# ahe_v1_0.net
KiCad netlist of a schematic drawn in EAGLE
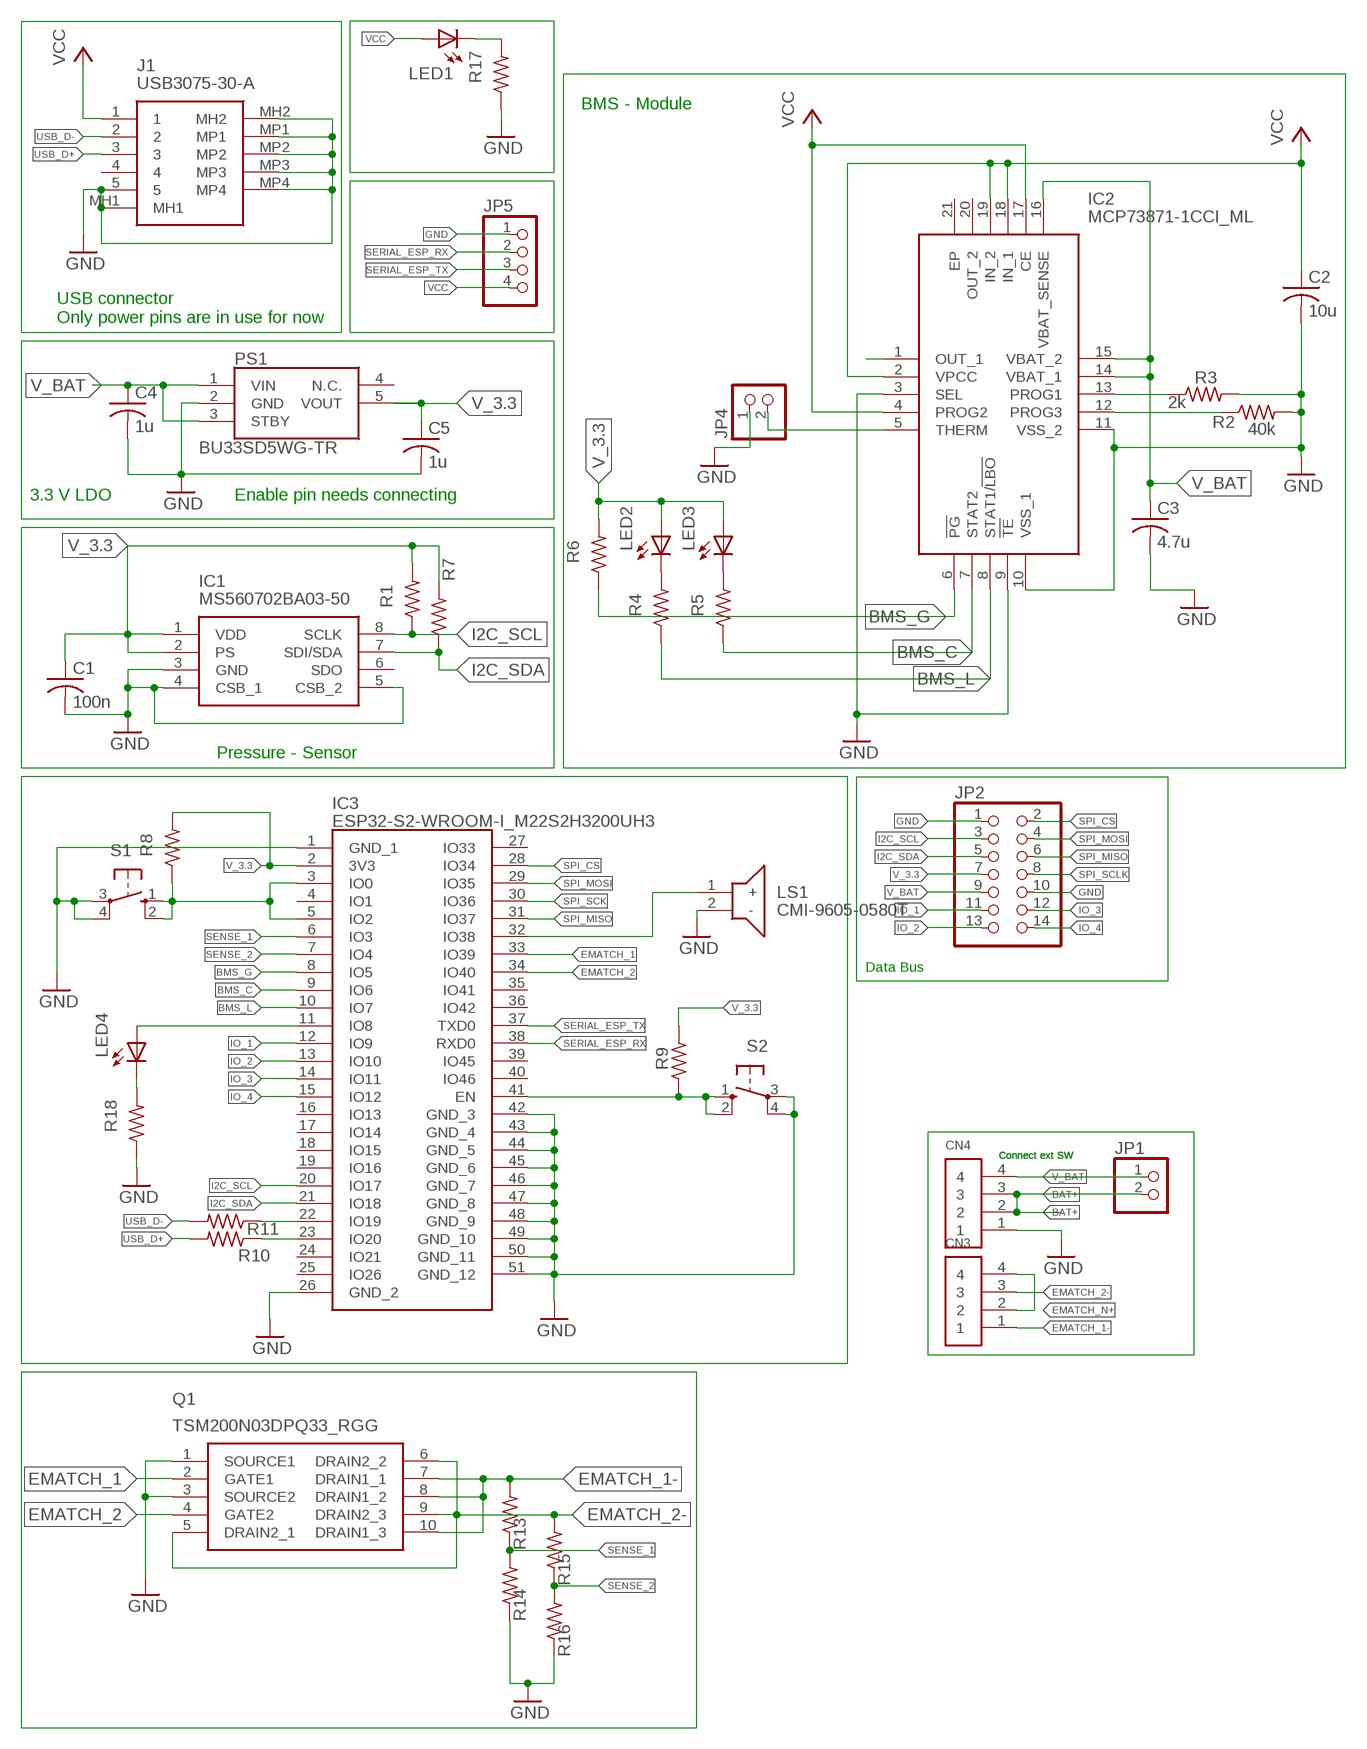
[diagram p0: schematic, sheet 1]

(export (version "E")
  (design (tool "Eeschema 10.0.6"))
  (components
    (comp (ref "C1")
      (value "100n")
      (footprint "eagle-import:C0805")
      (libsource (lib "eagle-import") (part "C-USC0805"))
    )
    (comp (ref "C2")
      (value "10u")
      (footprint "eagle-import:C0805")
      (libsource (lib "eagle-import") (part "C-USC0805"))
    )
    (comp (ref "C3")
      (value "4.7u")
      (footprint "eagle-import:C0805")
      (libsource (lib "eagle-import") (part "C-USC0805"))
    )
    (comp (ref "C4")
      (value "1u")
      (footprint "eagle-import:C0805")
      (libsource (lib "eagle-import") (part "C-USC0805"))
    )
    (comp (ref "C5")
      (value "1u")
      (footprint "eagle-import:C0805")
      (libsource (lib "eagle-import") (part "C-USC0805"))
    )
    (comp (ref "CN3")
      (value "1X4-3.5MM")
      (footprint "eagle-import:1X04-3.5MM")
      (libsource (lib "eagle-import") (part "1X4-3.5MM"))
    )
    (comp (ref "CN4")
      (value "1X4-3.5MM")
      (footprint "eagle-import:1X04-3.5MM")
      (libsource (lib "eagle-import") (part "1X4-3.5MM"))
    )
    (comp (ref "IC1")
      (value "MS560702BA03-50")
      (footprint "eagle-import:MS5607-02BA03")
      (fields (field (name "MOUSER_PART_NUMBER") "824-MS560702BA03-50"))
      (libsource (lib "eagle-import") (part "MS560702BA03-50"))
    )
    (comp (ref "IC2")
      (value "MCP73871-1CCI_ML")
      (footprint "eagle-import:QFN50P400X400X100-21N")
      (fields
        (field (name "MANUFACTURER_PART_NUMBER") "MCP73871-1CCI/ML")
        (field (name "MOUSER_PART_NUMBER") "579-MCP73871-1CCI/ML")
      )
      (libsource (lib "eagle-import") (part "MCP73871-1CCI_ML"))
    )
    (comp (ref "IC3")
      (value "ESP32-S2-WROOM-I_M22S2H3200UH3")
      (footprint "eagle-import:ESP32S2WROOMIM22S2H3200UH3Q0")
      (fields
        (field (name "MANUFACTURER_PART_NUMBER") "ESP32-S2-WROOM-I(M22S2H3200UH3Q0)")
        (field (name "MOUSER_PART_NUMBER") "356-ESP32S2WRMI320UH")
      )
      (libsource (lib "eagle-import") (part "ESP32-S2-WROOM-I_M22S2H3200UH3"))
    )
    (comp (ref "J1")
      (value "USB3075-30-A")
      (footprint "eagle-import:USB307530A")
      (fields (field (name "MOUSER_PART_NUMBER") "640-USB3075-30-A"))
      (libsource (lib "eagle-import") (part "USB3075-30-A"))
    )
    (comp (ref "JP1")
      (value "PINHD-1X2")
      (footprint "eagle-import:1X02")
      (libsource (lib "eagle-import") (part "PINHD-1X2"))
    )
    (comp (ref "JP2")
      (value "PINHD-2X7")
      (footprint "eagle-import:2X07")
      (libsource (lib "eagle-import") (part "PINHD-2X7"))
    )
    (comp (ref "JP4")
      (value "PINHD-1X2")
      (footprint "eagle-import:1X02")
      (libsource (lib "eagle-import") (part "PINHD-1X2"))
    )
    (comp (ref "JP5")
      (value "PINHD-1X4")
      (footprint "eagle-import:1X04")
      (libsource (lib "eagle-import") (part "PINHD-1X4"))
    )
    (comp (ref "LED1")
      (value "LEDCHIPLED_0805")
      (footprint "eagle-import:CHIPLED_0805")
      (libsource (lib "eagle-import") (part "LEDCHIPLED_0805"))
    )
    (comp (ref "LED2")
      (value "LEDCHIPLED_0805")
      (footprint "eagle-import:CHIPLED_0805")
      (libsource (lib "eagle-import") (part "LEDCHIPLED_0805"))
    )
    (comp (ref "LED3")
      (value "LEDCHIPLED_0805")
      (footprint "eagle-import:CHIPLED_0805")
      (libsource (lib "eagle-import") (part "LEDCHIPLED_0805"))
    )
    (comp (ref "LED4")
      (value "LEDCHIPLED_0805")
      (footprint "eagle-import:CHIPLED_0805")
      (libsource (lib "eagle-import") (part "LEDCHIPLED_0805"))
    )
    (comp (ref "LS1")
      (value "CMI-9605-0580T")
      (footprint "eagle-import:CMI96050580T")
      (fields (field (name "MOUSER_PART_NUMBER") "490-CMI-9605-0580T"))
      (libsource (lib "eagle-import") (part "CMI-9605-0580T"))
    )
    (comp (ref "PS1")
      (value "BU33SD5WG-TR")
      (footprint "eagle-import:SOT95P280X125-5N")
      (fields (field (name "MOUSER_PART_NUMBER") "755-BU33SD5WG-TR"))
      (libsource (lib "eagle-import") (part "BU33SD5WG-TR"))
    )
    (comp (ref "Q1")
      (value "TSM200N03DPQ33_RGG")
      (footprint "eagle-import:TSM200N03DPQ33RGG")
      (fields
        (field (name "MANUFACTURER_PART_NUMBER") "TSM200N03DPQ33 RGG")
        (field (name "MOUSER_PART_NUMBER") "821-TSM200N03DPQ33RG")
      )
      (libsource (lib "eagle-import") (part "TSM200N03DPQ33_RGG"))
    )
    (comp (ref "R1")
      (value "10k")
      (footprint "eagle-import:R0805")
      (libsource (lib "eagle-import") (part "R-US_R0805"))
    )
    (comp (ref "R2")
      (value "40k")
      (footprint "eagle-import:R0805")
      (libsource (lib "eagle-import") (part "R-US_R0805"))
    )
    (comp (ref "R3")
      (value "2k")
      (footprint "eagle-import:R0805")
      (libsource (lib "eagle-import") (part "R-US_R0805"))
    )
    (comp (ref "R4")
      (value "330")
      (footprint "eagle-import:R0805")
      (libsource (lib "eagle-import") (part "R-US_R0805"))
    )
    (comp (ref "R5")
      (value "330")
      (footprint "eagle-import:R0805")
      (libsource (lib "eagle-import") (part "R-US_R0805"))
    )
    (comp (ref "R6")
      (value "10k")
      (footprint "eagle-import:R0805")
      (libsource (lib "eagle-import") (part "R-US_R0805"))
    )
    (comp (ref "R7")
      (value "10k")
      (footprint "eagle-import:R0805")
      (libsource (lib "eagle-import") (part "R-US_R0805"))
    )
    (comp (ref "R8")
      (value "10k")
      (footprint "eagle-import:R0805")
      (libsource (lib "eagle-import") (part "R-US_R0805"))
    )
    (comp (ref "R9")
      (value "10k")
      (footprint "eagle-import:R0805")
      (libsource (lib "eagle-import") (part "R-US_R0805"))
    )
    (comp (ref "R10")
      (value "33")
      (footprint "eagle-import:R0805")
      (libsource (lib "eagle-import") (part "R-US_R0805"))
    )
    (comp (ref "R11")
      (value "33")
      (footprint "eagle-import:R0805")
      (libsource (lib "eagle-import") (part "R-US_R0805"))
    )
    (comp (ref "R13")
      (value "100k")
      (footprint "eagle-import:R0805")
      (libsource (lib "eagle-import") (part "R-US_R0805"))
    )
    (comp (ref "R14")
      (value "27k")
      (footprint "eagle-import:R0805")
      (libsource (lib "eagle-import") (part "R-US_R0805"))
    )
    (comp (ref "R15")
      (value "100k")
      (footprint "eagle-import:R0805")
      (libsource (lib "eagle-import") (part "R-US_R0805"))
    )
    (comp (ref "R16")
      (value "27k")
      (footprint "eagle-import:R0805")
      (libsource (lib "eagle-import") (part "R-US_R0805"))
    )
    (comp (ref "R17")
      (value "330")
      (footprint "eagle-import:R0805")
      (libsource (lib "eagle-import") (part "R-US_R0805"))
    )
    (comp (ref "R18")
      (value "330")
      (footprint "eagle-import:R0805")
      (libsource (lib "eagle-import") (part "R-US_R0805"))
    )
    (comp (ref "S1")
      (value "10-XX")
      (footprint "eagle-import:B3F-10XX")
      (fields (field (name "MPN") "B3F-1000"))
      (libsource (lib "eagle-import") (part "10-XX"))
    )
    (comp (ref "S2")
      (value "10-XX")
      (footprint "eagle-import:B3F-10XX")
      (fields (field (name "MPN") "B3F-1000"))
      (libsource (lib "eagle-import") (part "10-XX"))
    )
  )
  (nets
    (net (code "1") (name "BAT+") (class "Default")
      (node (ref "CN4") (pin "2") (pinfunction "2_2") (pintype "bidirectional"))
      (node (ref "CN4") (pin "3") (pinfunction "3_3") (pintype "bidirectional"))
      (node (ref "JP1") (pin "2") (pinfunction "2_2") (pintype "passive"))
    )
    (net (code "2") (name "BMS_C") (class "Default")
      (node (ref "IC2") (pin "7") (pinfunction "STAT2_7") (pintype "bidirectional"))
      (node (ref "IC3") (pin "9") (pinfunction "IO6_9") (pintype "bidirectional"))
      (node (ref "R5") (pin "1") (pinfunction "1_1") (pintype "passive"))
    )
    (net (code "3") (name "BMS_G") (class "Default")
      (node (ref "IC2") (pin "6") (pinfunction "~{PG}_6") (pintype "bidirectional"))
      (node (ref "IC3") (pin "8") (pinfunction "IO5_8") (pintype "bidirectional"))
      (node (ref "R6") (pin "1") (pinfunction "1_1") (pintype "passive"))
    )
    (net (code "4") (name "BMS_L") (class "Default")
      (node (ref "IC2") (pin "8") (pinfunction "STAT1/~{LBO}_8") (pintype "bidirectional"))
      (node (ref "IC3") (pin "10") (pinfunction "IO7_10") (pintype "bidirectional"))
      (node (ref "R4") (pin "1") (pinfunction "1_1") (pintype "passive"))
    )
    (net (code "5") (name "EMATCH_1") (class "Default")
      (node (ref "IC3") (pin "33") (pinfunction "IO39_33") (pintype "bidirectional"))
      (node (ref "Q1") (pin "2") (pinfunction "GATE1_2") (pintype "bidirectional"))
    )
    (net (code "6") (name "EMATCH_1-") (class "Default")
      (node (ref "CN3") (pin "1") (pinfunction "1_1") (pintype "bidirectional"))
      (node (ref "Q1") (pin "10") (pinfunction "DRAIN1_3_10") (pintype "bidirectional"))
      (node (ref "Q1") (pin "7") (pinfunction "DRAIN1_1_7") (pintype "bidirectional"))
      (node (ref "Q1") (pin "8") (pinfunction "DRAIN1_2_8") (pintype "bidirectional"))
      (node (ref "R13") (pin "2") (pinfunction "2_2") (pintype "passive"))
    )
    (net (code "7") (name "EMATCH_2") (class "Default")
      (node (ref "IC3") (pin "34") (pinfunction "IO40_34") (pintype "bidirectional"))
      (node (ref "Q1") (pin "4") (pinfunction "GATE2_4") (pintype "bidirectional"))
    )
    (net (code "8") (name "EMATCH_2-") (class "Default")
      (node (ref "CN3") (pin "3") (pinfunction "3_3") (pintype "bidirectional"))
      (node (ref "Q1") (pin "5") (pinfunction "DRAIN2_1_5") (pintype "bidirectional"))
      (node (ref "Q1") (pin "6") (pinfunction "DRAIN2_2_6") (pintype "bidirectional"))
      (node (ref "Q1") (pin "9") (pinfunction "DRAIN2_3_9") (pintype "bidirectional"))
      (node (ref "R15") (pin "2") (pinfunction "2_2") (pintype "passive"))
    )
    (net (code "9") (name "EMATCH_N+") (class "Default")
      (node (ref "CN3") (pin "2") (pinfunction "2_2") (pintype "bidirectional"))
      (node (ref "CN3") (pin "4") (pinfunction "4_4") (pintype "bidirectional"))
    )
    (net (code "10") (name "GND") (class "Default")
      (node (ref "C1") (pin "2") (pinfunction "2_2") (pintype "passive"))
      (node (ref "C2") (pin "2") (pinfunction "2_2") (pintype "passive"))
      (node (ref "C3") (pin "2") (pinfunction "2_2") (pintype "passive"))
      (node (ref "C4") (pin "2") (pinfunction "2_2") (pintype "passive"))
      (node (ref "C5") (pin "2") (pinfunction "2_2") (pintype "passive"))
      (node (ref "CN4") (pin "1") (pinfunction "1_1") (pintype "bidirectional"))
      (node (ref "IC1") (pin "3") (pinfunction "GND_3") (pintype "power_in"))
      (node (ref "IC1") (pin "4") (pinfunction "CSB_1_4") (pintype "input"))
      (node (ref "IC1") (pin "5") (pinfunction "CSB_2_5") (pintype "input"))
      (node (ref "IC2") (pin "10") (pinfunction "VSS_1_10") (pintype "bidirectional"))
      (node (ref "IC2") (pin "11") (pinfunction "VSS_2_11") (pintype "bidirectional"))
      (node (ref "IC2") (pin "3") (pinfunction "SEL_3") (pintype "bidirectional"))
      (node (ref "IC2") (pin "9") (pinfunction "~{TE}_9") (pintype "bidirectional"))
      (node (ref "IC3") (pin "1") (pinfunction "GND_1_1") (pintype "bidirectional"))
      (node (ref "IC3") (pin "26") (pinfunction "GND_2_26") (pintype "bidirectional"))
      (node (ref "IC3") (pin "42") (pinfunction "GND_3_42") (pintype "bidirectional"))
      (node (ref "IC3") (pin "43") (pinfunction "GND_4_43") (pintype "bidirectional"))
      (node (ref "IC3") (pin "44") (pinfunction "GND_5_44") (pintype "bidirectional"))
      (node (ref "IC3") (pin "45") (pinfunction "GND_6_45") (pintype "bidirectional"))
      (node (ref "IC3") (pin "46") (pinfunction "GND_7_46") (pintype "bidirectional"))
      (node (ref "IC3") (pin "47") (pinfunction "GND_8_47") (pintype "bidirectional"))
      (node (ref "IC3") (pin "48") (pinfunction "GND_9_48") (pintype "bidirectional"))
      (node (ref "IC3") (pin "49") (pinfunction "GND_10_49") (pintype "bidirectional"))
      (node (ref "IC3") (pin "50") (pinfunction "GND_11_50") (pintype "bidirectional"))
      (node (ref "IC3") (pin "51") (pinfunction "GND_12_51") (pintype "bidirectional"))
      (node (ref "J1") (pin "5") (pinfunction "5_5") (pintype "bidirectional"))
      (node (ref "J1") (pin "MH1") (pinfunction "MH1_MH1") (pintype "bidirectional"))
      (node (ref "J1") (pin "MH2") (pinfunction "MH2_MH2") (pintype "bidirectional"))
      (node (ref "J1") (pin "MP1") (pinfunction "MP1_MP1") (pintype "bidirectional"))
      (node (ref "J1") (pin "MP2") (pinfunction "MP2_MP2") (pintype "bidirectional"))
      (node (ref "J1") (pin "MP3") (pinfunction "MP3_MP3") (pintype "bidirectional"))
      (node (ref "J1") (pin "MP4") (pinfunction "MP4_MP4") (pintype "bidirectional"))
      (node (ref "JP2") (pin "1") (pinfunction "1_1") (pintype "passive"))
      (node (ref "JP2") (pin "10") (pinfunction "10_10") (pintype "passive"))
      (node (ref "JP4") (pin "1") (pinfunction "1_1") (pintype "passive"))
      (node (ref "JP5") (pin "1") (pinfunction "1_1") (pintype "passive"))
      (node (ref "LS1") (pin "2") (pinfunction "-_2") (pintype "bidirectional"))
      (node (ref "PS1") (pin "2") (pinfunction "GND_2") (pintype "bidirectional"))
      (node (ref "Q1") (pin "1") (pinfunction "SOURCE1_1") (pintype "bidirectional"))
      (node (ref "Q1") (pin "3") (pinfunction "SOURCE2_3") (pintype "bidirectional"))
      (node (ref "R14") (pin "1") (pinfunction "1_1") (pintype "passive"))
      (node (ref "R16") (pin "1") (pinfunction "1_1") (pintype "passive"))
      (node (ref "R17") (pin "1") (pinfunction "1_1") (pintype "passive"))
      (node (ref "R18") (pin "1") (pinfunction "1_1") (pintype "passive"))
      (node (ref "R2") (pin "2") (pinfunction "2_2") (pintype "passive"))
      (node (ref "R3") (pin "2") (pinfunction "2_2") (pintype "passive"))
      (node (ref "S1") (pin "3") (pinfunction "P_3") (pintype "passive"))
      (node (ref "S1") (pin "4") (pinfunction "P1_4") (pintype "passive"))
      (node (ref "S2") (pin "3") (pinfunction "P_3") (pintype "passive"))
      (node (ref "S2") (pin "4") (pinfunction "P1_4") (pintype "passive"))
    )
    (net (code "11") (name "I2C_SCL") (class "Default")
      (node (ref "IC1") (pin "8") (pinfunction "SCLK_8") (pintype "input"))
      (node (ref "IC3") (pin "20") (pinfunction "IO17_20") (pintype "bidirectional"))
      (node (ref "JP2") (pin "3") (pinfunction "3_3") (pintype "passive"))
      (node (ref "R1") (pin "1") (pinfunction "1_1") (pintype "passive"))
    )
    (net (code "12") (name "I2C_SDA") (class "Default")
      (node (ref "IC1") (pin "7") (pinfunction "SDI/SDA_7") (pintype "bidirectional"))
      (node (ref "IC3") (pin "21") (pinfunction "IO18_21") (pintype "bidirectional"))
      (node (ref "JP2") (pin "5") (pinfunction "5_5") (pintype "passive"))
      (node (ref "R7") (pin "1") (pinfunction "1_1") (pintype "passive"))
    )
    (net (code "13") (name "IO_1") (class "Default")
      (node (ref "IC3") (pin "12") (pinfunction "IO9_12") (pintype "bidirectional"))
      (node (ref "JP2") (pin "11") (pinfunction "11_11") (pintype "passive"))
    )
    (net (code "14") (name "IO_2") (class "Default")
      (node (ref "IC3") (pin "13") (pinfunction "IO10_13") (pintype "bidirectional"))
      (node (ref "JP2") (pin "13") (pinfunction "13_13") (pintype "passive"))
    )
    (net (code "15") (name "IO_3") (class "Default")
      (node (ref "IC3") (pin "14") (pinfunction "IO11_14") (pintype "bidirectional"))
      (node (ref "JP2") (pin "12") (pinfunction "12_12") (pintype "passive"))
    )
    (net (code "16") (name "IO_4") (class "Default")
      (node (ref "IC3") (pin "15") (pinfunction "IO12_15") (pintype "bidirectional"))
      (node (ref "JP2") (pin "14") (pinfunction "14_14") (pintype "passive"))
    )
    (net (code "17") (name "Net-(IC2-PROG1)") (class "Default")
      (node (ref "IC2") (pin "13") (pinfunction "PROG1_13") (pintype "bidirectional"))
      (node (ref "R3") (pin "1") (pinfunction "1_1") (pintype "passive"))
    )
    (net (code "18") (name "Net-(IC2-PROG3)") (class "Default")
      (node (ref "IC2") (pin "12") (pinfunction "PROG3_12") (pintype "bidirectional"))
      (node (ref "R2") (pin "1") (pinfunction "1_1") (pintype "passive"))
    )
    (net (code "19") (name "Net-(IC2-THERM)") (class "Default")
      (node (ref "IC2") (pin "5") (pinfunction "THERM_5") (pintype "bidirectional"))
      (node (ref "JP4") (pin "2") (pinfunction "2_2") (pintype "passive"))
    )
    (net (code "20") (name "Net-(IC3-EN)") (class "Default")
      (node (ref "IC3") (pin "41") (pinfunction "EN_41") (pintype "bidirectional"))
      (node (ref "R9") (pin "1") (pinfunction "1_1") (pintype "passive"))
      (node (ref "S2") (pin "1") (pinfunction "S_1") (pintype "passive"))
      (node (ref "S2") (pin "2") (pinfunction "S1_2") (pintype "passive"))
    )
    (net (code "21") (name "Net-(IC3-IO0)") (class "Default")
      (node (ref "IC3") (pin "3") (pinfunction "IO0_3") (pintype "bidirectional"))
      (node (ref "IC3") (pin "5") (pinfunction "IO2_5") (pintype "bidirectional"))
      (node (ref "R8") (pin "1") (pinfunction "1_1") (pintype "passive"))
      (node (ref "S1") (pin "1") (pinfunction "S_1") (pintype "passive"))
      (node (ref "S1") (pin "2") (pinfunction "S1_2") (pintype "passive"))
    )
    (net (code "22") (name "Net-(IC3-IO8)") (class "Default")
      (node (ref "IC3") (pin "11") (pinfunction "IO8_11") (pintype "bidirectional"))
      (node (ref "LED4") (pin "A") (pinfunction "A_A") (pintype "passive"))
    )
    (net (code "23") (name "Net-(IC3-IO19)") (class "Default")
      (node (ref "IC3") (pin "22") (pinfunction "IO19_22") (pintype "bidirectional"))
      (node (ref "R11") (pin "1") (pinfunction "1_1") (pintype "passive"))
    )
    (net (code "24") (name "Net-(IC3-IO20)") (class "Default")
      (node (ref "IC3") (pin "23") (pinfunction "IO20_23") (pintype "bidirectional"))
      (node (ref "R10") (pin "1") (pinfunction "1_1") (pintype "passive"))
    )
    (net (code "25") (name "Net-(IC3-IO38)") (class "Default")
      (node (ref "IC3") (pin "32") (pinfunction "IO38_32") (pintype "bidirectional"))
      (node (ref "LS1") (pin "1") (pinfunction "+_1") (pintype "bidirectional"))
    )
    (net (code "26") (name "Net-(LED1-PadC)") (class "Default")
      (node (ref "LED1") (pin "C") (pinfunction "C_C") (pintype "passive"))
      (node (ref "R17") (pin "2") (pinfunction "2_2") (pintype "passive"))
    )
    (net (code "27") (name "Net-(LED2-PadC)") (class "Default")
      (node (ref "LED2") (pin "C") (pinfunction "C_C") (pintype "passive"))
      (node (ref "R4") (pin "2") (pinfunction "2_2") (pintype "passive"))
    )
    (net (code "28") (name "Net-(LED3-PadC)") (class "Default")
      (node (ref "LED3") (pin "C") (pinfunction "C_C") (pintype "passive"))
      (node (ref "R5") (pin "2") (pinfunction "2_2") (pintype "passive"))
    )
    (net (code "29") (name "Net-(LED4-PadC)") (class "Default")
      (node (ref "LED4") (pin "C") (pinfunction "C_C") (pintype "passive"))
      (node (ref "R18") (pin "2") (pinfunction "2_2") (pintype "passive"))
    )
    (net (code "30") (name "SENSE_1") (class "Default")
      (node (ref "IC3") (pin "6") (pinfunction "IO3_6") (pintype "bidirectional"))
      (node (ref "R13") (pin "1") (pinfunction "1_1") (pintype "passive"))
      (node (ref "R14") (pin "2") (pinfunction "2_2") (pintype "passive"))
    )
    (net (code "31") (name "SENSE_2") (class "Default")
      (node (ref "IC3") (pin "7") (pinfunction "IO4_7") (pintype "bidirectional"))
      (node (ref "R15") (pin "1") (pinfunction "1_1") (pintype "passive"))
      (node (ref "R16") (pin "2") (pinfunction "2_2") (pintype "passive"))
    )
    (net (code "32") (name "SERIAL_ESP_RX") (class "Default")
      (node (ref "IC3") (pin "38") (pinfunction "RXD0_38") (pintype "bidirectional"))
      (node (ref "JP5") (pin "2") (pinfunction "2_2") (pintype "passive"))
    )
    (net (code "33") (name "SERIAL_ESP_TX") (class "Default")
      (node (ref "IC3") (pin "37") (pinfunction "TXD0_37") (pintype "bidirectional"))
      (node (ref "JP5") (pin "3") (pinfunction "3_3") (pintype "passive"))
    )
    (net (code "34") (name "SPI_CS") (class "Default")
      (node (ref "IC3") (pin "28") (pinfunction "IO34_28") (pintype "bidirectional"))
      (node (ref "JP2") (pin "2") (pinfunction "2_2") (pintype "passive"))
    )
    (net (code "35") (name "SPI_MISO") (class "Default")
      (node (ref "IC3") (pin "31") (pinfunction "IO37_31") (pintype "bidirectional"))
      (node (ref "JP2") (pin "6") (pinfunction "6_6") (pintype "passive"))
    )
    (net (code "36") (name "SPI_MOSI") (class "Default")
      (node (ref "IC3") (pin "29") (pinfunction "IO35_29") (pintype "bidirectional"))
      (node (ref "JP2") (pin "4") (pinfunction "4_4") (pintype "passive"))
    )
    (net (code "37") (name "SPI_SCK") (class "Default")
      (node (ref "IC3") (pin "30") (pinfunction "IO36_30") (pintype "bidirectional"))
    )
    (net (code "38") (name "SPI_SCLK") (class "Default")
      (node (ref "JP2") (pin "8") (pinfunction "8_8") (pintype "passive"))
    )
    (net (code "39") (name "USB_D+") (class "Default")
      (node (ref "J1") (pin "3") (pinfunction "3_3") (pintype "bidirectional"))
      (node (ref "R10") (pin "2") (pinfunction "2_2") (pintype "passive"))
    )
    (net (code "40") (name "USB_D-") (class "Default")
      (node (ref "J1") (pin "2") (pinfunction "2_2") (pintype "bidirectional"))
      (node (ref "R11") (pin "2") (pinfunction "2_2") (pintype "passive"))
    )
    (net (code "41") (name "VCC") (class "Default")
      (node (ref "C2") (pin "1") (pinfunction "1_1") (pintype "passive"))
      (node (ref "IC2") (pin "17") (pinfunction "CE_17") (pintype "bidirectional"))
      (node (ref "IC2") (pin "18") (pinfunction "IN_1_18") (pintype "bidirectional"))
      (node (ref "IC2") (pin "19") (pinfunction "IN_2_19") (pintype "bidirectional"))
      (node (ref "IC2") (pin "2") (pinfunction "VPCC_2") (pintype "bidirectional"))
      (node (ref "IC2") (pin "4") (pinfunction "PROG2_4") (pintype "bidirectional"))
      (node (ref "J1") (pin "1") (pinfunction "1_1") (pintype "bidirectional"))
      (node (ref "JP5") (pin "4") (pinfunction "4_4") (pintype "passive"))
      (node (ref "LED1") (pin "A") (pinfunction "A_A") (pintype "passive"))
    )
    (net (code "42") (name "V_3.3") (class "Default")
      (node (ref "C1") (pin "1") (pinfunction "1_1") (pintype "passive"))
      (node (ref "C5") (pin "1") (pinfunction "1_1") (pintype "passive"))
      (node (ref "IC1") (pin "1") (pinfunction "VDD_1") (pintype "power_in"))
      (node (ref "IC1") (pin "2") (pinfunction "PS_2") (pintype "input"))
      (node (ref "IC3") (pin "2") (pinfunction "3V3_2") (pintype "bidirectional"))
      (node (ref "JP2") (pin "7") (pinfunction "7_7") (pintype "passive"))
      (node (ref "LED2") (pin "A") (pinfunction "A_A") (pintype "passive"))
      (node (ref "LED3") (pin "A") (pinfunction "A_A") (pintype "passive"))
      (node (ref "PS1") (pin "5") (pinfunction "VOUT_5") (pintype "bidirectional"))
      (node (ref "R1") (pin "2") (pinfunction "2_2") (pintype "passive"))
      (node (ref "R6") (pin "2") (pinfunction "2_2") (pintype "passive"))
      (node (ref "R7") (pin "2") (pinfunction "2_2") (pintype "passive"))
      (node (ref "R8") (pin "2") (pinfunction "2_2") (pintype "passive"))
      (node (ref "R9") (pin "2") (pinfunction "2_2") (pintype "passive"))
    )
    (net (code "43") (name "V_BAT") (class "Default")
      (node (ref "C3") (pin "1") (pinfunction "1_1") (pintype "passive"))
      (node (ref "C4") (pin "1") (pinfunction "1_1") (pintype "passive"))
      (node (ref "CN4") (pin "4") (pinfunction "4_4") (pintype "bidirectional"))
      (node (ref "IC2") (pin "14") (pinfunction "VBAT_1_14") (pintype "bidirectional"))
      (node (ref "IC2") (pin "15") (pinfunction "VBAT_2_15") (pintype "bidirectional"))
      (node (ref "IC2") (pin "16") (pinfunction "VBAT_SENSE_16") (pintype "bidirectional"))
      (node (ref "JP1") (pin "1") (pinfunction "1_1") (pintype "passive"))
      (node (ref "JP2") (pin "9") (pinfunction "9_9") (pintype "passive"))
      (node (ref "PS1") (pin "1") (pinfunction "VIN_1") (pintype "bidirectional"))
      (node (ref "PS1") (pin "3") (pinfunction "STBY_3") (pintype "bidirectional"))
    )
    (net (code "44") (name "unconnected-(IC1-SDO-Pad6)") (class "Default")
      (node (ref "IC1") (pin "6") (pinfunction "SDO_6") (pintype "output"))
    )
    (net (code "45") (name "unconnected-(IC2-EP-Pad21)") (class "Default")
      (node (ref "IC2") (pin "21") (pinfunction "EP_21") (pintype "bidirectional"))
    )
    (net (code "46") (name "unconnected-(IC2-OUT_1-Pad1)") (class "Default")
      (node (ref "IC2") (pin "1") (pinfunction "OUT_1_1") (pintype "bidirectional"))
    )
    (net (code "47") (name "unconnected-(IC2-OUT_2-Pad20)") (class "Default")
      (node (ref "IC2") (pin "20") (pinfunction "OUT_2_20") (pintype "bidirectional"))
    )
    (net (code "48") (name "unconnected-(IC3-IO1-Pad4)") (class "Default")
      (node (ref "IC3") (pin "4") (pinfunction "IO1_4") (pintype "bidirectional"))
    )
    (net (code "49") (name "unconnected-(IC3-IO13-Pad16)") (class "Default")
      (node (ref "IC3") (pin "16") (pinfunction "IO13_16") (pintype "bidirectional"))
    )
    (net (code "50") (name "unconnected-(IC3-IO14-Pad17)") (class "Default")
      (node (ref "IC3") (pin "17") (pinfunction "IO14_17") (pintype "bidirectional"))
    )
    (net (code "51") (name "unconnected-(IC3-IO15-Pad18)") (class "Default")
      (node (ref "IC3") (pin "18") (pinfunction "IO15_18") (pintype "bidirectional"))
    )
    (net (code "52") (name "unconnected-(IC3-IO16-Pad19)") (class "Default")
      (node (ref "IC3") (pin "19") (pinfunction "IO16_19") (pintype "bidirectional"))
    )
    (net (code "53") (name "unconnected-(IC3-IO21-Pad24)") (class "Default")
      (node (ref "IC3") (pin "24") (pinfunction "IO21_24") (pintype "bidirectional"))
    )
    (net (code "54") (name "unconnected-(IC3-IO26-Pad25)") (class "Default")
      (node (ref "IC3") (pin "25") (pinfunction "IO26_25") (pintype "bidirectional"))
    )
    (net (code "55") (name "unconnected-(IC3-IO33-Pad27)") (class "Default")
      (node (ref "IC3") (pin "27") (pinfunction "IO33_27") (pintype "bidirectional"))
    )
    (net (code "56") (name "unconnected-(IC3-IO41-Pad35)") (class "Default")
      (node (ref "IC3") (pin "35") (pinfunction "IO41_35") (pintype "bidirectional"))
    )
    (net (code "57") (name "unconnected-(IC3-IO42-Pad36)") (class "Default")
      (node (ref "IC3") (pin "36") (pinfunction "IO42_36") (pintype "bidirectional"))
    )
    (net (code "58") (name "unconnected-(IC3-IO45-Pad39)") (class "Default")
      (node (ref "IC3") (pin "39") (pinfunction "IO45_39") (pintype "bidirectional"))
    )
    (net (code "59") (name "unconnected-(IC3-IO46-Pad40)") (class "Default")
      (node (ref "IC3") (pin "40") (pinfunction "IO46_40") (pintype "bidirectional"))
    )
    (net (code "60") (name "unconnected-(J1-Pad4)") (class "Default")
      (node (ref "J1") (pin "4") (pinfunction "4_4") (pintype "bidirectional"))
    )
    (net (code "61") (name "unconnected-(PS1-N.C.-Pad4)") (class "Default")
      (node (ref "PS1") (pin "4") (pinfunction "N.C._4") (pintype "no_connect"))
    )
  )
)
